# Voltage_Regulation.net
KiCad netlist of a schematic drawn in Altium Designer
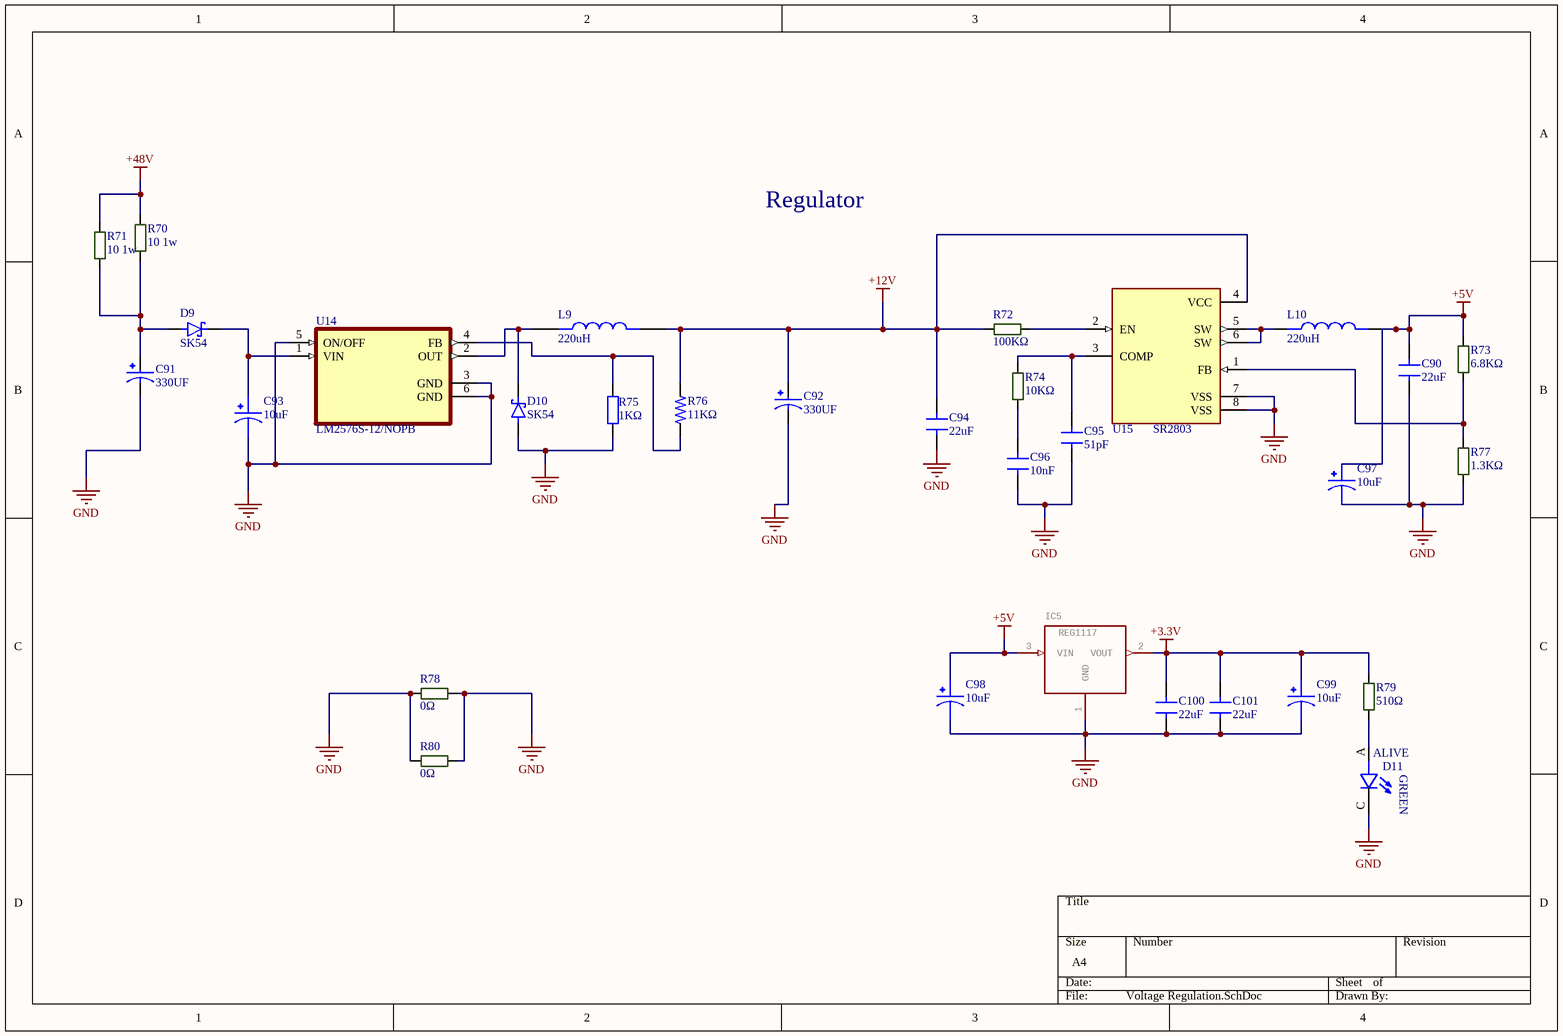
[diagram p0: Voltage Regulation.SchDoc]

(export (version "E")
  (design (tool "Eeschema 10.0.6"))
  (components
    (comp (ref "C90")
      (value "22uF")
      (footprint "C-0805")
      (libsource (lib "Gate Driver Board") (part "C-0805"))
    )
    (comp (ref "C91")
      (value "330UF")
      (footprint "CAP_EEETC1C331V")
      (description "CAP ALUM 330UF 20% 16V SMD")
      (fields (field (name "MP") "EEE-TC1C331V") (field (name "MF") "Panasonic Electronic Components"))
      (libsource (lib "PROJE") (part "CAP 330UF SMD"))
    )
    (comp (ref "C92")
      (value "330UF")
      (footprint "CAP_EEETC1C331V")
      (description "CAP ALUM 330UF 20% 16V SMD")
      (fields (field (name "MP") "EEE-TC1C331V") (field (name "MF") "Panasonic Electronic Components"))
      (libsource (lib "PROJE") (part "CAP 330UF SMD"))
    )
    (comp (ref "C93")
      (value "10uF")
      (footprint "CapSmdElc")
      (libsource (lib "PROJE") (part "100 uF Electr Cap"))
    )
    (comp (ref "C94")
      (value "22uF")
      (footprint "C-0805")
      (libsource (lib "Gate Driver Board") (part "C-0805"))
    )
    (comp (ref "C95")
      (value "51pF")
      (footprint "C-0603W")
      (libsource (lib "Gate Driver Board") (part "C-0603"))
    )
    (comp (ref "C96")
      (value "10nF")
      (footprint "C-0805")
      (libsource (lib "Gate Driver Board") (part "C-0805"))
    )
    (comp (ref "C97")
      (value "10uF")
      (footprint "CapSmdElc")
      (libsource (lib "PROJE") (part "100 uF Electr Cap"))
    )
    (comp (ref "C98")
      (value "10uF")
      (footprint "CapSmdElc")
      (libsource (lib "PROJE") (part "100 uF Electr Cap"))
    )
    (comp (ref "C99")
      (value "10uF")
      (footprint "CapSmdElc")
      (libsource (lib "PROJE") (part "100 uF Electr Cap"))
    )
    (comp (ref "C100")
      (value "22uF")
      (footprint "C-0805")
      (libsource (lib "Gate Driver Board") (part "C-0805"))
    )
    (comp (ref "C101")
      (value "22uF")
      (footprint "C-0805")
      (libsource (lib "Gate Driver Board") (part "C-0805"))
    )
    (comp (ref "D9")
      (value "SK54")
      (footprint "DIOM7959X265N")
      (description "Diode Schottky 40V 5A Surface Mount DO-214AA (SMB)")
      (fields (field (name "MP") "MBRS320T3G") (field (name "MF") "ON Semiconductor"))
      (libsource (lib "PROJE") (part "SK54"))
    )
    (comp (ref "D10")
      (value "SK54")
      (footprint "DIOM7959X265N")
      (description "Diode Schottky 40V 5A Surface Mount DO-214AA (SMB)")
      (fields (field (name "MP") "MBRS320T3G") (field (name "MF") "ON Semiconductor"))
      (libsource (lib "PROJE") (part "SK54"))
    )
    (comp (ref "D11")
      (value "ALIVE")
      (footprint "LED_7012X1")
      (description "Green LED Indication - Discrete 1.7V 0805 (2012 Metric)")
      (fields (field (name "MP") "7012X1"))
      (libsource (lib "Gate Driver Board") (part "ALIVE"))
    )
    (comp (ref "IC5")
      (value "REG1117")
      (footprint "SOT223")
      (description "800mA and 1A Low Dropout (LDO) Positive Regulator   1.8V, 2.5V, 2.85V, 3.3V, 5V, and Adj")
      (fields (field (name "MF") "MF") (field (name "LIBRARYNAME") "burr-brown"))
      (libsource (lib "Gate Driver Board") (part "REG1117"))
    )
    (comp (ref "L9")
      (value "220uH")
      (footprint "IND_MDH12577C-101MA=P3")
      (description "Inductor Power Shielded Wirewound 220uH 20% 100KHz Ferrite 1.1A 0.325Ohm DCR 5049 Automotive T/R")
      (fields (field (name "MP") "MDH12577C-101MA=P3"))
      (libsource (lib "PROJE") (part "220uH Inductor SMD"))
    )
    (comp (ref "L10")
      (value "220uH")
      (footprint "IND_MDH12577C-101MA=P3")
      (description "Inductor Power Shielded Wirewound 220uH 20% 100KHz Ferrite 1.1A 0.325Ohm DCR 5049 Automotive T/R")
      (fields (field (name "MP") "MDH12577C-101MA=P3"))
      (libsource (lib "PROJE") (part "220uH Inductor SMD"))
    )
    (comp (ref "R70")
      (value "10 1w")
      (footprint "R-2512")
      (libsource (lib "Gate Driver Board") (part "R-2512"))
    )
    (comp (ref "R71")
      (value "10 1w")
      (footprint "R-2512")
      (libsource (lib "Gate Driver Board") (part "R-2512"))
    )
    (comp (ref "R72")
      (value "100KΩ")
      (footprint "R-0805")
      (libsource (lib "Gate Driver Board") (part "R-0805"))
    )
    (comp (ref "R73")
      (value "6.8KΩ")
      (footprint "R-0603R")
      (libsource (lib "Gate Driver Board") (part "R-0603"))
    )
    (comp (ref "R74")
      (value "10KΩ")
      (footprint "R-0805")
      (libsource (lib "Gate Driver Board") (part "R-0805"))
    )
    (comp (ref "R75")
      (value "RES SMD 1K OHM 1% 1/8W 0805")
      (footprint "R-0805")
      (description "1 kOhms ±1% 0.125W, 1/8W Chip Resistor 0805 (2012 Metric) Moisture Resistant Thick Film")
      (fields (field (name "DEGER") "1KΩ"))
      (libsource (lib "PROJE") (part "1K 0805"))
    )
    (comp (ref "R76")
      (value "11KΩ")
      (footprint "R-0805")
      (description "THICK FILM RESISTOR, 11KOHM, 125mW, 5%")
      (fields (field (name "MP") "CRCW080511K0JNEA"))
      (libsource (lib "PROJE") (part "RES 11KΩ SMD"))
    )
    (comp (ref "R77")
      (value "1.3KΩ")
      (footprint "R-0603R")
      (libsource (lib "Gate Driver Board") (part "R-0603"))
    )
    (comp (ref "R78")
      (value "0Ω")
      (footprint "R-2512")
      (description "10 1w")
      (libsource (lib "Gate Driver Board") (part "R-2512"))
    )
    (comp (ref "R79")
      (value "510Ω")
      (footprint "R-0603R")
      (libsource (lib "Gate Driver Board") (part "R-0603"))
    )
    (comp (ref "R80")
      (value "0Ω")
      (footprint "R-2512")
      (description "10 1w")
      (libsource (lib "Gate Driver Board") (part "R-2512"))
    )
    (comp (ref "U14")
      (value "LM2576S-12/NOPB")
      (footprint "VREG_TPS79625KTTR")
      (description "SIMPLE SWITCHER&reg; 40V, 3A Low Component Count Step-Down Regulator 5-DDPAK/TO-263 -40 to 125")
      (fields
        (field (name "MF") "Texas Instruments")
        (field (name "BUYPART") "https://www.snapeda.com/parts/LM2576S-12/NOPB/Texas%20Instruments/view-part/470772/?ref=eda")
      )
      (libsource (lib "PROJE") (part "LM2576S-12/NOPB"))
    )
    (comp (ref "U15")
      (value "SR2803")
      (footprint "SOP127P600X175-8N")
      (description "330KHZ, 3A SYNCHRONOUS\r\nBUCK CONTROLLER")
      (fields (field (name "MF") "Taiwan Semiconductor Corporation") (field (name "MP") "TS2509CS RLG"))
      (libsource (lib "Gate Driver Board") (part "SR2803"))
    )
  )
  (nets
    (net (code "1") (name "+3.3V") (class "Default")
      (node (ref "C100") (pin "2") (pinfunction "2_2") (pintype "passive"))
      (node (ref "C101") (pin "2") (pinfunction "2_2") (pintype "passive"))
      (node (ref "C99") (pin "1") (pinfunction "1_1") (pintype "passive"))
      (node (ref "IC5") (pin "2") (pinfunction "VOUT_2") (pintype "output"))
      (node (ref "R79") (pin "2") (pinfunction "2_2") (pintype "passive"))
    )
    (net (code "2") (name "+5V") (class "Default")
      (node (ref "C90") (pin "2") (pinfunction "2_2") (pintype "passive"))
      (node (ref "C97") (pin "1") (pinfunction "1_1") (pintype "passive"))
      (node (ref "C98") (pin "1") (pinfunction "1_1") (pintype "passive"))
      (node (ref "IC5") (pin "3") (pinfunction "VIN_3") (pintype "input"))
      (node (ref "L10") (pin "2") (pinfunction "2_2") (pintype "passive"))
      (node (ref "R73") (pin "2") (pinfunction "2_2") (pintype "passive"))
    )
    (net (code "3") (name "+12V") (class "Default")
      (node (ref "C92") (pin "1") (pinfunction "1_1") (pintype "passive"))
      (node (ref "C94") (pin "2") (pinfunction "2_2") (pintype "passive"))
      (node (ref "L9") (pin "2") (pinfunction "2_2") (pintype "passive"))
      (node (ref "R72") (pin "2") (pinfunction "2_2") (pintype "passive"))
      (node (ref "R76") (pin "2") (pinfunction "2_2") (pintype "passive"))
      (node (ref "U15") (pin "4") (pinfunction "VCC_4") (pintype "power_in"))
    )
    (net (code "4") (name "+48V") (class "Default")
      (node (ref "R70") (pin "2") (pinfunction "2_2") (pintype "passive"))
      (node (ref "R71") (pin "2") (pinfunction "2_2") (pintype "passive"))
    )
    (net (code "5") (name "GND") (class "Default")
      (node (ref "C100") (pin "1") (pinfunction "1_1") (pintype "passive"))
      (node (ref "C101") (pin "1") (pinfunction "1_1") (pintype "passive"))
      (node (ref "C90") (pin "1") (pinfunction "1_1") (pintype "passive"))
      (node (ref "C91") (pin "2") (pinfunction "2_2") (pintype "passive"))
      (node (ref "C92") (pin "2") (pinfunction "2_2") (pintype "passive"))
      (node (ref "C93") (pin "2") (pinfunction "2_2") (pintype "passive"))
      (node (ref "C94") (pin "1") (pinfunction "1_1") (pintype "passive"))
      (node (ref "C95") (pin "1") (pinfunction "1_1") (pintype "passive"))
      (node (ref "C96") (pin "1") (pinfunction "1_1") (pintype "passive"))
      (node (ref "C97") (pin "2") (pinfunction "2_2") (pintype "passive"))
      (node (ref "C98") (pin "2") (pinfunction "2_2") (pintype "passive"))
      (node (ref "C99") (pin "2") (pinfunction "2_2") (pintype "passive"))
      (node (ref "D10") (pin "A") (pinfunction "A_A") (pintype "passive"))
      (node (ref "D11") (pin "C") (pinfunction "C_C") (pintype "passive"))
      (node (ref "IC5") (pin "1") (pinfunction "GND_1") (pintype "power_in"))
      (node (ref "R75") (pin "1") (pinfunction "1_1") (pintype "passive"))
      (node (ref "R77") (pin "1") (pinfunction "1_1") (pintype "passive"))
      (node (ref "R78") (pin "1") (pinfunction "1_1") (pintype "passive"))
      (node (ref "R78") (pin "2") (pinfunction "2_2") (pintype "passive"))
      (node (ref "R80") (pin "1") (pinfunction "1_1") (pintype "passive"))
      (node (ref "R80") (pin "2") (pinfunction "2_2") (pintype "passive"))
      (node (ref "U14") (pin "3") (pinfunction "GND_3") (pintype "power_in"))
      (node (ref "U14") (pin "5") (pinfunction "ON/OFF_5") (pintype "input"))
      (node (ref "U14") (pin "6") (pinfunction "GND_6") (pintype "power_in"))
      (node (ref "U15") (pin "7") (pinfunction "VSS_7") (pintype "power_in"))
      (node (ref "U15") (pin "8") (pinfunction "VSS_8") (pintype "power_in"))
    )
    (net (code "6") (name "Net-(C91-Pad1)") (class "Default")
      (node (ref "C91") (pin "1") (pinfunction "1_1") (pintype "passive"))
      (node (ref "D9") (pin "A") (pinfunction "A_A") (pintype "passive"))
      (node (ref "R70") (pin "1") (pinfunction "1_1") (pintype "passive"))
      (node (ref "R71") (pin "1") (pinfunction "1_1") (pintype "passive"))
    )
    (net (code "7") (name "Net-(C96-Pad2)") (class "Default")
      (node (ref "C96") (pin "2") (pinfunction "2_2") (pintype "passive"))
      (node (ref "R74") (pin "1") (pinfunction "1_1") (pintype "passive"))
    )
    (net (code "8") (name "Net-(D9-K)") (class "Default")
      (node (ref "C93") (pin "1") (pinfunction "1_1") (pintype "passive"))
      (node (ref "D9") (pin "C") (pinfunction "K_C") (pintype "passive"))
      (node (ref "U14") (pin "1") (pinfunction "VIN_1") (pintype "input"))
    )
    (net (code "9") (name "Net-(D10-K)") (class "Default")
      (node (ref "D10") (pin "C") (pinfunction "K_C") (pintype "passive"))
      (node (ref "L9") (pin "1") (pinfunction "1_1") (pintype "passive"))
      (node (ref "U14") (pin "2") (pinfunction "OUT_2") (pintype "output"))
    )
    (net (code "10") (name "Net-(D11-PadA)") (class "Default")
      (node (ref "D11") (pin "A") (pinfunction "A_A") (pintype "passive"))
      (node (ref "R79") (pin "1") (pinfunction "1_1") (pintype "passive"))
    )
    (net (code "11") (name "Net-(L10-Pad1)") (class "Default")
      (node (ref "L10") (pin "1") (pinfunction "1_1") (pintype "passive"))
      (node (ref "U15") (pin "5") (pinfunction "SW_5") (pintype "output"))
      (node (ref "U15") (pin "6") (pinfunction "SW_6") (pintype "output"))
    )
    (net (code "12") (name "Net-(U14-FB)") (class "Default")
      (node (ref "R75") (pin "2") (pinfunction "2_2") (pintype "passive"))
      (node (ref "R76") (pin "1") (pinfunction "1_1") (pintype "passive"))
      (node (ref "U14") (pin "4") (pinfunction "FB_4") (pintype "output"))
    )
    (net (code "13") (name "Net-(U15-COMP)") (class "Default")
      (node (ref "C95") (pin "2") (pinfunction "2_2") (pintype "passive"))
      (node (ref "R74") (pin "2") (pinfunction "2_2") (pintype "passive"))
      (node (ref "U15") (pin "3") (pinfunction "COMP_3") (pintype "passive"))
    )
    (net (code "14") (name "Net-(U15-EN)") (class "Default")
      (node (ref "R72") (pin "1") (pinfunction "1_1") (pintype "passive"))
      (node (ref "U15") (pin "2") (pinfunction "EN_2") (pintype "input"))
    )
    (net (code "15") (name "Net-(U15-FB)") (class "Default")
      (node (ref "R73") (pin "1") (pinfunction "1_1") (pintype "passive"))
      (node (ref "R77") (pin "2") (pinfunction "2_2") (pintype "passive"))
      (node (ref "U15") (pin "1") (pinfunction "FB_1") (pintype "input"))
    )
  )
)
